# cSLIM-SA_GPS.net
KiCad netlist of a schematic drawn in Altium Designer
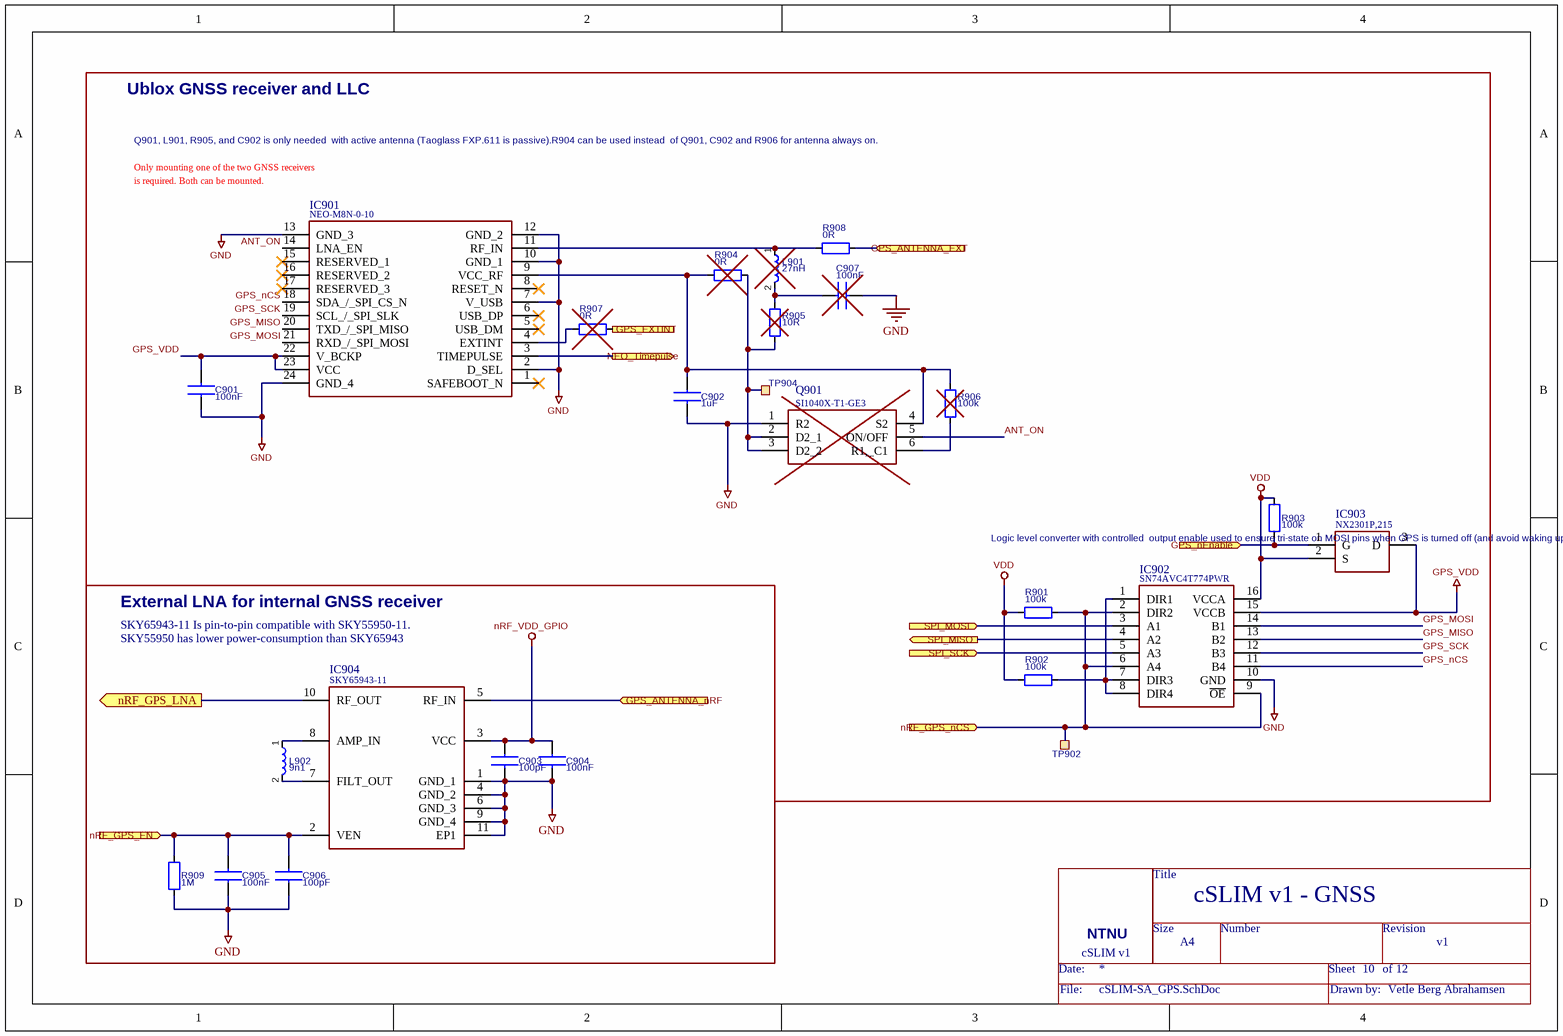
[diagram p0: cSLIM-SA_GPS.SchDoc]

(export (version "E")
  (design (tool "Eeschema 10.0.6"))
  (components
    (comp (ref "C901")
      (value "100nF")
      (footprint "cSLIM-SA:CAPC1608X90N")
      (description "Capacitor")
      (fields (field (name "MANUFACTURER_PART_NUMBER") "CL10B104KB8NNNL"))
      (libsource (lib "cSLIM-SA") (part "C"))
    )
    (comp (ref "C902")
      (value "1uF")
      (footprint "cSLIM-SA:CAPC1608X90N")
      (description "Capacitor")
      (fields (field (name "MANUFACTURER_PART_NUMBER") "CL10A105KO8NNNC"))
      (libsource (lib "cSLIM-SA") (part "C"))
    )
    (comp (ref "C903")
      (value "100pF")
      (footprint "cSLIM-SA:CAPC1608X90N")
      (description "Capacitor")
      (fields (field (name "MANUFACTURER_PART_NUMBER") "CL10C101JB8NNNC"))
      (libsource (lib "cSLIM-SA") (part "C"))
    )
    (comp (ref "C904")
      (value "100nF")
      (footprint "cSLIM-SA:CAPC1608X90N")
      (description "Capacitor")
      (fields (field (name "MANUFACTURER_PART_NUMBER") "CL10B104KB8NNNL"))
      (libsource (lib "cSLIM-SA") (part "C"))
    )
    (comp (ref "C905")
      (value "100nF")
      (footprint "cSLIM-SA:CAPC1608X90N")
      (description "Capacitor")
      (fields (field (name "MANUFACTURER_PART_NUMBER") "CL10B104KB8NNNL"))
      (libsource (lib "cSLIM-SA") (part "C"))
    )
    (comp (ref "C906")
      (value "100pF")
      (footprint "cSLIM-SA:CAPC1608X90N")
      (description "Capacitor")
      (fields (field (name "MANUFACTURER_PART_NUMBER") "CL10C101JB8NNNC"))
      (libsource (lib "cSLIM-SA") (part "C"))
    )
    (comp (ref "C907")
      (value "100nF")
      (footprint "cSLIM-SA:CAPC1608X90N")
      (description "Capacitor")
      (fields (field (name "MANUFACTURER_PART_NUMBER") "CL10B104KB8NNNL"))
      (libsource (lib "cSLIM-SA") (part "C"))
    )
    (comp (ref "IC901")
      (value "NEO-M8N-0-10")
      (footprint "cSLIM-SA:NEOM9N00B")
      (description "NEO-M9N-00B should be used if available")
      (fields (field (name "MOUSER PART NUMBER") "377-NEO-M9N-00B"))
      (libsource (lib "cSLIM-SA") (part "NEO-M9N-00B"))
    )
    (comp (ref "IC902")
      (value "SN74AVC4T774PWR")
      (footprint "cSLIM-SA:SOP65P640X120-16N")
      (description "Logic Level Converter (LLC)")
      (fields (field (name "MOUSER PART NUMBER") "595-SN74AVC4T774PWR"))
      (libsource (lib "cSLIM-SA") (part "SN74AVC4T774PWR"))
    )
    (comp (ref "IC903")
      (value "NX2301P,215")
      (footprint "cSLIM-SA:SOT95P230X110-3N")
      (description "P-Channel 20V 2A (Ta) 400mW (Ta), 2.8W (Tc) Surface Mount TO-236AB")
      (fields (field (name "MOUSER PART NUMBER") "771-NX2301P215"))
      (libsource (lib "cSLIM-SA") (part "NX2301P,215"))
    )
    (comp (ref "IC904")
      (value "SKY65943-11")
      (footprint "cSLIM-SA:SKY6594311")
      (description "GPS LNA MODULE")
      (fields (field (name "MOUSER PART NUMBER") "873-SKY65943-11"))
      (libsource (lib "cSLIM-SA") (part "SKY65943-11"))
    )
    (comp (ref "L901")
      (value "27nH")
      (footprint "cSLIM-SA:L-1608")
      (fields (field (name "MANUFACTURER_PART_NUMBER") "LQG18HH27NJ00D"))
      (libsource (lib "cSLIM-SA") (part "L"))
    )
    (comp (ref "L902")
      (value "9n1")
      (footprint "cSLIM-SA:LQW18AS10NG0CD")
      (fields (field (name "MANUFACTURER_PART_NUMBER") "LQW18AN9N1D00D"))
      (libsource (lib "cSLIM-SA") (part "L_1"))
    )
    (comp (ref "Q901")
      (value "SI1040X-T1-GE3")
      (footprint "cSLIM-SA:SOTFL50P160X60-6N")
      (description "IC PWR SWITCH P-CHAN 1:1 SC89-6")
      (fields (field (name "MOUSER PART NUMBER") "781-SI1040X-T1-GE3"))
      (libsource (lib "cSLIM-SA") (part "SI1040X-T1-GE3"))
    )
    (comp (ref "R901")
      (value "100k")
      (footprint "cSLIM-SA:RESC1608X55N")
      (fields (field (name "MANUFACTURER_PART_NUMBER") "RC0603FR-07100KL"))
      (libsource (lib "cSLIM-SA") (part "R"))
    )
    (comp (ref "R902")
      (value "100k")
      (footprint "cSLIM-SA:RESC1608X55N")
      (fields (field (name "MANUFACTURER_PART_NUMBER") "RC0603FR-07100KL"))
      (libsource (lib "cSLIM-SA") (part "R"))
    )
    (comp (ref "R903")
      (value "100k")
      (footprint "cSLIM-SA:RESC1608X55N")
      (fields (field (name "MANUFACTURER_PART_NUMBER") "RC0603FR-07100KL"))
      (libsource (lib "") (part "R_1"))
    )
    (comp (ref "R904")
      (value "0R")
      (footprint "cSLIM-SA:RESC1608X55N")
      (fields (field (name "MANUFACTURER_PART_NUMBER") "YJP1608-R001"))
      (libsource (lib "cSLIM-SA") (part "R"))
    )
    (comp (ref "R905")
      (value "10R")
      (footprint "cSLIM-SA:RESC1608X55N")
      (fields (field (name "MANUFACTURER_PART_NUMBER") "RC0603FR-1310RL"))
      (libsource (lib "") (part "R_1"))
    )
    (comp (ref "R906")
      (value "100k")
      (footprint "cSLIM-SA:RESC1608X55N")
      (fields (field (name "MANUFACTURER_PART_NUMBER") "RC0603FR-07100KL"))
      (libsource (lib "") (part "R_1"))
    )
    (comp (ref "R907")
      (value "0R")
      (footprint "cSLIM-SA:RESC1608X55N")
      (fields (field (name "MANUFACTURER_PART_NUMBER") "YJP1608-R001"))
      (libsource (lib "") (part "R_2"))
    )
    (comp (ref "R908")
      (value "0R")
      (footprint "cSLIM-SA:RESC1608X55N")
      (fields (field (name "MANUFACTURER_PART_NUMBER") "YJP1608-R001"))
      (libsource (lib "cSLIM-SA") (part "R"))
    )
    (comp (ref "R909")
      (value "1M")
      (footprint "cSLIM-SA:RESC1608X55N")
      (fields (field (name "MANUFACTURER_PART_NUMBER") "RC0603FR-131ML"))
      (libsource (lib "") (part "R_3"))
    )
    (comp (ref "TP902")
      (value "TP")
      (footprint "cSLIM-SA:TP_SMD_Ø1.0mm")
      (description "Test points")
      (libsource (lib "cSLIM-SA") (part "TP"))
    )
    (comp (ref "TP904")
      (value "TP")
      (footprint "cSLIM-SA:TP_SMD_Ø1.0mm")
      (description "Test points")
      (libsource (lib "") (part "TP_1"))
    )
  )
  (nets
    (net (code "1") (name "/ANT_ON") (class "Default")
      (node (ref "IC901") (pin "14") (pinfunction "LNA_EN_14") (pintype "passive"))
      (node (ref "Q901") (pin "5") (pinfunction "ON/OFF_5") (pintype "passive"))
    )
    (net (code "2") (name "/GPS_ANTENNA_EXT") (class "Default")
      (node (ref "R908") (pin "1") (pinfunction "1_1") (pintype "passive"))
    )
    (net (code "3") (name "/GPS_ANTENNA_nRF") (class "Default")
      (node (ref "IC904") (pin "5") (pinfunction "RF_IN_5") (pintype "passive"))
    )
    (net (code "4") (name "/GPS_EXTINT") (class "Default")
      (node (ref "R907") (pin "2") (pinfunction "2_2") (pintype "passive"))
    )
    (net (code "5") (name "/GPS_MISO") (class "Default")
      (node (ref "IC901") (pin "20") (pinfunction "TXD_/_SPI_MISO_20") (pintype "passive"))
      (node (ref "IC902") (pin "13") (pinfunction "B2_13") (pintype "passive"))
    )
    (net (code "6") (name "/GPS_MOSI") (class "Default")
      (node (ref "IC901") (pin "21") (pinfunction "RXD_/_SPI_MOSI_21") (pintype "passive"))
      (node (ref "IC902") (pin "14") (pinfunction "B1_14") (pintype "passive"))
    )
    (net (code "7") (name "/GPS_SCK") (class "Default")
      (node (ref "IC901") (pin "19") (pinfunction "SCL_/_SPI_SLK_19") (pintype "passive"))
      (node (ref "IC902") (pin "12") (pinfunction "B3_12") (pintype "passive"))
    )
    (net (code "8") (name "/GPS_nCS") (class "Default")
      (node (ref "IC901") (pin "18") (pinfunction "SDA_/_SPI_CS_N_18") (pintype "passive"))
      (node (ref "IC902") (pin "11") (pinfunction "B4_11") (pintype "passive"))
    )
    (net (code "9") (name "/GPS_nEnable") (class "Default")
      (node (ref "IC903") (pin "1") (pinfunction "G_1") (pintype "passive"))
      (node (ref "R903") (pin "1") (pinfunction "1_1") (pintype "passive"))
    )
    (net (code "10") (name "/NEO_Timepulse") (class "Default")
      (node (ref "IC901") (pin "3") (pinfunction "TIMEPULSE_3") (pintype "passive"))
    )
    (net (code "11") (name "/SPI_MISO") (class "Default")
      (node (ref "IC902") (pin "4") (pinfunction "A2_4") (pintype "passive"))
    )
    (net (code "12") (name "/SPI_MOSI") (class "Default")
      (node (ref "IC902") (pin "3") (pinfunction "A1_3") (pintype "passive"))
    )
    (net (code "13") (name "/SPI_SCK") (class "Default")
      (node (ref "IC902") (pin "5") (pinfunction "A3_5") (pintype "passive"))
    )
    (net (code "14") (name "/nRF_GPS_EN") (class "Default")
      (node (ref "C905") (pin "2") (pinfunction "2_2") (pintype "passive"))
      (node (ref "C906") (pin "2") (pinfunction "2_2") (pintype "passive"))
      (node (ref "IC904") (pin "2") (pinfunction "VEN_2") (pintype "passive"))
      (node (ref "R909") (pin "1") (pinfunction "1_1") (pintype "passive"))
    )
    (net (code "15") (name "/nRF_GPS_LNA") (class "Default")
      (node (ref "IC904") (pin "10") (pinfunction "RF_OUT_10") (pintype "passive"))
    )
    (net (code "16") (name "/nRF_GPS_nCS") (class "Default")
      (node (ref "IC902") (pin "2") (pinfunction "DIR2_2") (pintype "passive"))
      (node (ref "IC902") (pin "6") (pinfunction "A4_6") (pintype "passive"))
      (node (ref "IC902") (pin "9") (pinfunction "~{OE}_9") (pintype "passive"))
      (node (ref "R901") (pin "1") (pinfunction "1_1") (pintype "passive"))
      (node (ref "TP902") (pin "1") (pinfunction "1_1") (pintype "passive"))
    )
    (net (code "17") (name "GND") (class "Default")
      (node (ref "C901") (pin "2") (pinfunction "2_2") (pintype "passive"))
      (node (ref "C902") (pin "2") (pinfunction "2_2") (pintype "passive"))
      (node (ref "C903") (pin "1") (pinfunction "1_1") (pintype "passive"))
      (node (ref "C904") (pin "1") (pinfunction "1_1") (pintype "passive"))
      (node (ref "C905") (pin "1") (pinfunction "1_1") (pintype "passive"))
      (node (ref "C906") (pin "1") (pinfunction "1_1") (pintype "passive"))
      (node (ref "C907") (pin "2") (pinfunction "2_2") (pintype "passive"))
      (node (ref "IC901") (pin "10") (pinfunction "GND_1_10") (pintype "passive"))
      (node (ref "IC901") (pin "12") (pinfunction "GND_2_12") (pintype "passive"))
      (node (ref "IC901") (pin "13") (pinfunction "GND_3_13") (pintype "passive"))
      (node (ref "IC901") (pin "2") (pinfunction "D_SEL_2") (pintype "passive"))
      (node (ref "IC901") (pin "24") (pinfunction "GND_4_24") (pintype "passive"))
      (node (ref "IC901") (pin "7") (pinfunction "V_USB_7") (pintype "passive"))
      (node (ref "IC902") (pin "10") (pinfunction "GND_10") (pintype "passive"))
      (node (ref "IC904") (pin "1") (pinfunction "GND_1_1") (pintype "passive"))
      (node (ref "IC904") (pin "11") (pinfunction "EP1_11") (pintype "passive"))
      (node (ref "IC904") (pin "4") (pinfunction "GND_2_4") (pintype "passive"))
      (node (ref "IC904") (pin "6") (pinfunction "GND_3_6") (pintype "passive"))
      (node (ref "IC904") (pin "9") (pinfunction "GND_4_9") (pintype "passive"))
      (node (ref "Q901") (pin "1") (pinfunction "R2_1") (pintype "passive"))
      (node (ref "R909") (pin "2") (pinfunction "2_2") (pintype "passive"))
    )
    (net (code "18") (name "GPS_VDD") (class "Default")
      (node (ref "C901") (pin "1") (pinfunction "1_1") (pintype "passive"))
      (node (ref "IC901") (pin "22") (pinfunction "V_BCKP_22") (pintype "passive"))
      (node (ref "IC901") (pin "23") (pinfunction "VCC_23") (pintype "passive"))
      (node (ref "IC902") (pin "15") (pinfunction "VCCB_15") (pintype "passive"))
      (node (ref "IC903") (pin "3") (pinfunction "D_3") (pintype "passive"))
    )
    (net (code "19") (name "Net-(C907-Pad1)") (class "Default")
      (node (ref "C907") (pin "1") (pinfunction "1_1") (pintype "passive"))
      (node (ref "L901") (pin "2") (pinfunction "2_2") (pintype "passive"))
      (node (ref "R905") (pin "2") (pinfunction "2_2") (pintype "passive"))
    )
    (net (code "20") (name "Net-(IC901-EXTINT)") (class "Default")
      (node (ref "IC901") (pin "4") (pinfunction "EXTINT_4") (pintype "passive"))
      (node (ref "R907") (pin "1") (pinfunction "1_1") (pintype "passive"))
    )
    (net (code "21") (name "Net-(IC901-RF_IN)") (class "Default")
      (node (ref "IC901") (pin "11") (pinfunction "RF_IN_11") (pintype "passive"))
      (node (ref "L901") (pin "1") (pinfunction "1_1") (pintype "passive"))
      (node (ref "R908") (pin "2") (pinfunction "2_2") (pintype "passive"))
    )
    (net (code "22") (name "Net-(IC901-VCC_RF)") (class "Default")
      (node (ref "C902") (pin "1") (pinfunction "1_1") (pintype "passive"))
      (node (ref "IC901") (pin "9") (pinfunction "VCC_RF_9") (pintype "passive"))
      (node (ref "Q901") (pin "4") (pinfunction "S2_4") (pintype "passive"))
      (node (ref "R904") (pin "2") (pinfunction "2_2") (pintype "passive"))
      (node (ref "R906") (pin "2") (pinfunction "2_2") (pintype "passive"))
    )
    (net (code "23") (name "Net-(IC902-DIR1)") (class "Default")
      (node (ref "IC902") (pin "1") (pinfunction "DIR1_1") (pintype "passive"))
      (node (ref "IC902") (pin "7") (pinfunction "DIR3_7") (pintype "passive"))
      (node (ref "IC902") (pin "8") (pinfunction "DIR4_8") (pintype "passive"))
      (node (ref "R902") (pin "1") (pinfunction "1_1") (pintype "passive"))
    )
    (net (code "24") (name "Net-(IC904-AMP_IN)") (class "Default")
      (node (ref "IC904") (pin "8") (pinfunction "AMP_IN_8") (pintype "passive"))
      (node (ref "L902") (pin "1") (pinfunction "1_1") (pintype "passive"))
    )
    (net (code "25") (name "Net-(IC904-FILT_OUT)") (class "Default")
      (node (ref "IC904") (pin "7") (pinfunction "FILT_OUT_7") (pintype "passive"))
      (node (ref "L902") (pin "2") (pinfunction "2_2") (pintype "passive"))
    )
    (net (code "26") (name "Net-(Q901-D2_1)") (class "Default")
      (node (ref "Q901") (pin "2") (pinfunction "D2_1_2") (pintype "passive"))
      (node (ref "Q901") (pin "3") (pinfunction "D2_2_3") (pintype "passive"))
      (node (ref "R904") (pin "1") (pinfunction "1_1") (pintype "passive"))
      (node (ref "R905") (pin "1") (pinfunction "1_1") (pintype "passive"))
      (node (ref "TP904") (pin "1") (pinfunction "1_1") (pintype "passive"))
    )
    (net (code "27") (name "Net-(Q901-R1,_C1)") (class "Default")
      (node (ref "Q901") (pin "6") (pinfunction "R1,_C1_6") (pintype "passive"))
      (node (ref "R906") (pin "1") (pinfunction "1_1") (pintype "passive"))
    )
    (net (code "28") (name "VDD") (class "Default")
      (node (ref "IC902") (pin "16") (pinfunction "VCCA_16") (pintype "passive"))
      (node (ref "IC903") (pin "2") (pinfunction "S_2") (pintype "passive"))
      (node (ref "R901") (pin "2") (pinfunction "2_2") (pintype "passive"))
      (node (ref "R902") (pin "2") (pinfunction "2_2") (pintype "passive"))
      (node (ref "R903") (pin "2") (pinfunction "2_2") (pintype "passive"))
    )
    (net (code "29") (name "nRF_VDD_GPIO") (class "Default")
      (node (ref "C903") (pin "2") (pinfunction "2_2") (pintype "passive"))
      (node (ref "C904") (pin "2") (pinfunction "2_2") (pintype "passive"))
      (node (ref "IC904") (pin "3") (pinfunction "VCC_3") (pintype "passive"))
    )
    (net (code "30") (name "unconnected-(IC901-RESERVED_1-Pad15)") (class "Default")
      (node (ref "IC901") (pin "15") (pinfunction "RESERVED_1_15") (pintype "passive+no_connect"))
    )
    (net (code "31") (name "unconnected-(IC901-RESERVED_2-Pad16)") (class "Default")
      (node (ref "IC901") (pin "16") (pinfunction "RESERVED_2_16") (pintype "passive+no_connect"))
    )
    (net (code "32") (name "unconnected-(IC901-RESERVED_3-Pad17)") (class "Default")
      (node (ref "IC901") (pin "17") (pinfunction "RESERVED_3_17") (pintype "passive+no_connect"))
    )
    (net (code "33") (name "unconnected-(IC901-RESET_N-Pad8)") (class "Default")
      (node (ref "IC901") (pin "8") (pinfunction "RESET_N_8") (pintype "passive+no_connect"))
    )
    (net (code "34") (name "unconnected-(IC901-SAFEBOOT_N-Pad1)") (class "Default")
      (node (ref "IC901") (pin "1") (pinfunction "SAFEBOOT_N_1") (pintype "passive+no_connect"))
    )
    (net (code "35") (name "unconnected-(IC901-USB_DM-Pad5)") (class "Default")
      (node (ref "IC901") (pin "5") (pinfunction "USB_DM_5") (pintype "passive+no_connect"))
    )
    (net (code "36") (name "unconnected-(IC901-USB_DP-Pad6)") (class "Default")
      (node (ref "IC901") (pin "6") (pinfunction "USB_DP_6") (pintype "passive+no_connect"))
    )
  )
)
